# stm32l021.net
KiCad netlist of a schematic drawn in EAGLE
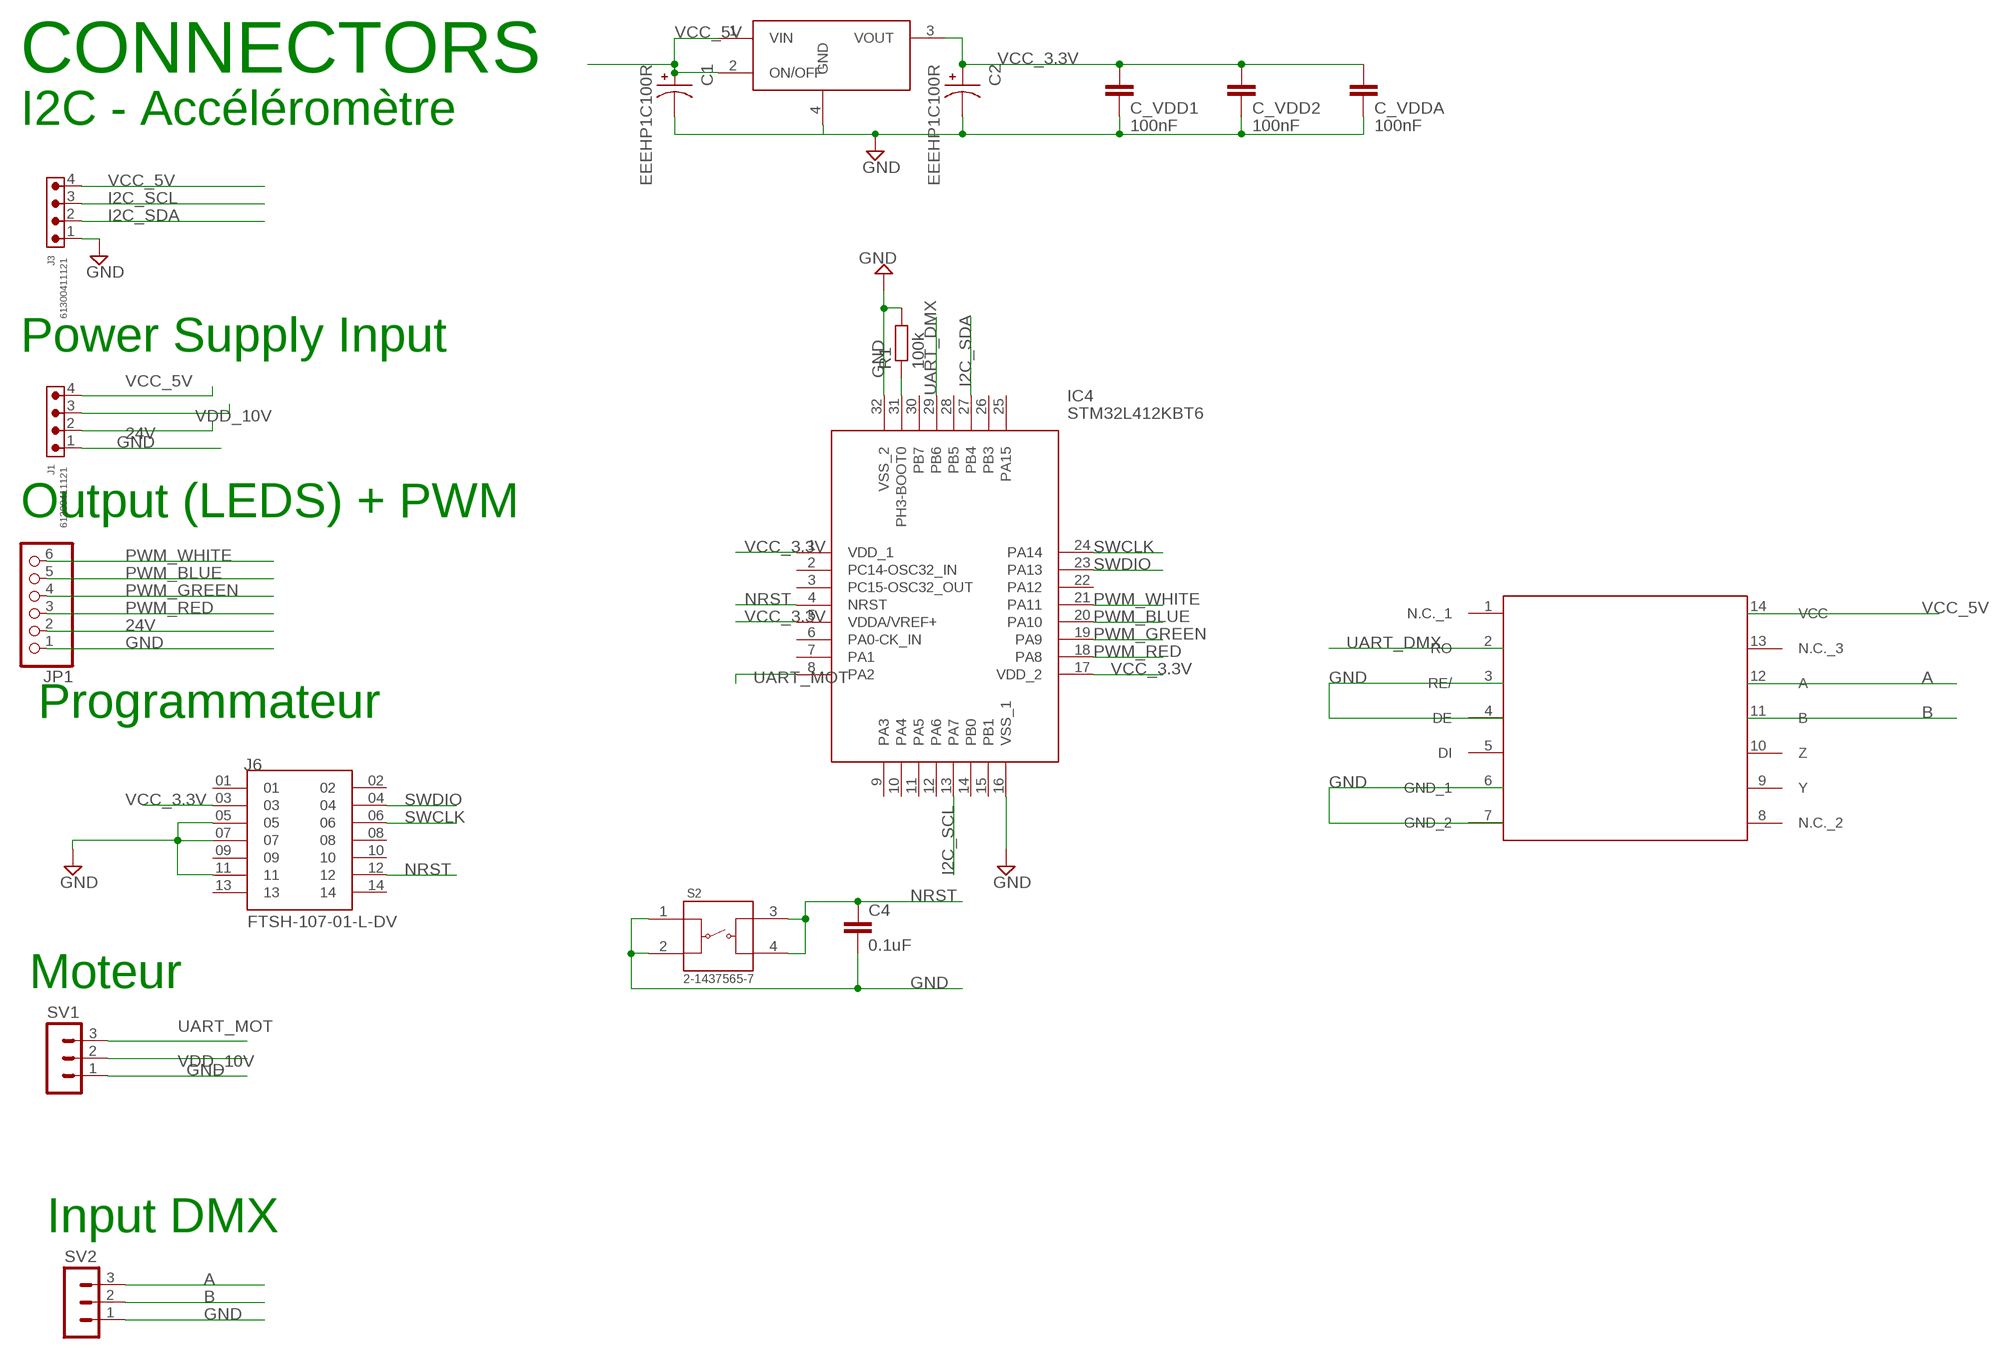
[diagram p0: schematic, sheet 1]

(export (version "E")
  (design (tool "Eeschema 10.0.6"))
  (components
    (comp (ref "C1")
      (value "EEEHP1C100R")
      (footprint "eagle-import:CAP_EEEHP1C100R")
      (fields (field (name "MF") "Panasonic"))
      (libsource (lib "eagle-import") (part "EEEHP1C100R"))
    )
    (comp (ref "C2")
      (value "EEEHP1C100R")
      (footprint "eagle-import:CAP_EEEHP1C100R")
      (fields (field (name "MF") "Panasonic"))
      (libsource (lib "eagle-import") (part "EEEHP1C100R"))
    )
    (comp (ref "C4")
      (value "0.1uF")
      (footprint "eagle-import:C0603")
      (libsource (lib "eagle-import") (part "C-EUC0603"))
    )
    (comp (ref "C_VDD1")
      (value "100nF")
      (footprint "eagle-import:C0603")
      (libsource (lib "eagle-import") (part "C-EUC0603"))
    )
    (comp (ref "C_VDD2")
      (value "100nF")
      (footprint "eagle-import:C0603")
      (libsource (lib "eagle-import") (part "C-EUC0603"))
    )
    (comp (ref "C_VDDA")
      (value "100nF")
      (footprint "eagle-import:C0603")
      (libsource (lib "eagle-import") (part "C-EUC0603"))
    )
    (comp (ref "IC4")
      (value "STM32L412KBT6")
      (footprint "eagle-import:QFP80P900X900X160-32N")
      (fields (field (name "MOUSER_PART_NUMBER") "511-STM32L412KBT6"))
      (libsource (lib "eagle-import") (part "STM32L412KBT6"))
    )
    (comp (ref "J1")
      (value "61300411121")
      (footprint "eagle-import:61300411121")
      (libsource (lib "eagle-import") (part "6130XX11121_61300411121"))
    )
    (comp (ref "J3")
      (value "61300411121")
      (footprint "eagle-import:61300411121")
      (libsource (lib "eagle-import") (part "6130XX11121_61300411121"))
    )
    (comp (ref "J6")
      (value "FTSH-107-01-L-DV")
      (footprint "eagle-import:SAMTEC_FTSH-107-01-L-DV")
      (fields (field (name "MANUFACTURER") "Samtec"))
      (libsource (lib "eagle-import") (part "FTSH-107-01-L-DV"))
    )
    (comp (ref "JP1")
      (value "PINHD-1X6")
      (footprint "eagle-import:1X06")
      (libsource (lib "eagle-import") (part "PINHD-1X6"))
    )
    (comp (ref "R1")
      (value "100k")
      (footprint "eagle-import:R0603")
      (libsource (lib "eagle-import") (part "R-EU_R0603"))
    )
    (comp (ref "S2")
      (value "2-1437565-7")
      (footprint "eagle-import:SW_2-1437565-7")
      (fields (field (name "MF") "TE Connectivity") (field (name "MP") "FSM2JSMA"))
      (libsource (lib "eagle-import") (part "2-1437565-7"))
    )
    (comp (ref "SV1")
      (value "MA03-1")
      (footprint "eagle-import:MA03-1")
      (libsource (lib "eagle-import") (part "MA03-1"))
    )
    (comp (ref "SV2")
      (value "MA03-1")
      (footprint "eagle-import:MA03-1")
      (libsource (lib "eagle-import") (part "MA03-1"))
    )
    (comp (ref "U$1")
      (value "NCV33375ST3.3T3G")
      (footprint "eagle-import:VREG_NCP1117STAT3G")
      (libsource (lib "eagle-import") (part "NCV33375ST3.3T3G"))
    )
    (comp (ref "U1")
      (value "SOIC127P600X175-14N")
      (footprint "eagle-import:SOIC127P600X175-14N")
      (fields (field (name "MANUFACTURER") "Maxim Integrated"))
      (libsource (lib "eagle-import") (part "SOIC127P600X175-14N"))
    )
  )
  (nets
    (net (code "1") (name "/24V") (class "Default")
      (node (ref "J1") (pin "2") (pinfunction "2_2") (pintype "passive"))
      (node (ref "JP1") (pin "2") (pinfunction "2_2") (pintype "passive"))
    )
    (net (code "2") (name "/A") (class "Default")
      (node (ref "SV2") (pin "3") (pinfunction "3_3") (pintype "passive"))
      (node (ref "U1") (pin "12") (pinfunction "A_12") (pintype "bidirectional"))
    )
    (net (code "3") (name "/B") (class "Default")
      (node (ref "SV2") (pin "2") (pinfunction "2_2") (pintype "passive"))
      (node (ref "U1") (pin "11") (pinfunction "B_11") (pintype "bidirectional"))
    )
    (net (code "4") (name "/I2C_SCL") (class "Default")
      (node (ref "IC4") (pin "13") (pinfunction "PA7_13") (pintype "bidirectional"))
      (node (ref "J3") (pin "3") (pinfunction "3_3") (pintype "passive"))
    )
    (net (code "5") (name "/I2C_SDA") (class "Default")
      (node (ref "IC4") (pin "27") (pinfunction "PB4_27") (pintype "bidirectional"))
      (node (ref "J3") (pin "2") (pinfunction "2_2") (pintype "passive"))
    )
    (net (code "6") (name "/NRST") (class "Default")
      (node (ref "C4") (pin "1") (pinfunction "1_1") (pintype "passive"))
      (node (ref "IC4") (pin "4") (pinfunction "NRST_4") (pintype "input"))
      (node (ref "J6") (pin "12") (pinfunction "12_12") (pintype "passive"))
      (node (ref "S2") (pin "3") (pinfunction "3_3") (pintype "passive"))
      (node (ref "S2") (pin "4") (pinfunction "4_4") (pintype "passive"))
    )
    (net (code "7") (name "/PWM_BLUE") (class "Default")
      (node (ref "IC4") (pin "20") (pinfunction "PA10_20") (pintype "bidirectional"))
      (node (ref "JP1") (pin "5") (pinfunction "5_5") (pintype "passive"))
    )
    (net (code "8") (name "/PWM_GREEN") (class "Default")
      (node (ref "IC4") (pin "19") (pinfunction "PA9_19") (pintype "bidirectional"))
      (node (ref "JP1") (pin "4") (pinfunction "4_4") (pintype "passive"))
    )
    (net (code "9") (name "/PWM_RED") (class "Default")
      (node (ref "IC4") (pin "18") (pinfunction "PA8_18") (pintype "bidirectional"))
      (node (ref "JP1") (pin "3") (pinfunction "3_3") (pintype "passive"))
    )
    (net (code "10") (name "/PWM_WHITE") (class "Default")
      (node (ref "IC4") (pin "21") (pinfunction "PA11_21") (pintype "bidirectional"))
      (node (ref "JP1") (pin "6") (pinfunction "6_6") (pintype "passive"))
    )
    (net (code "11") (name "/SWCLK") (class "Default")
      (node (ref "IC4") (pin "24") (pinfunction "PA14_24") (pintype "bidirectional"))
      (node (ref "J6") (pin "06") (pinfunction "06_06") (pintype "passive"))
    )
    (net (code "12") (name "/SWDIO") (class "Default")
      (node (ref "IC4") (pin "23") (pinfunction "PA13_23") (pintype "bidirectional"))
      (node (ref "J6") (pin "04") (pinfunction "04_04") (pintype "passive"))
    )
    (net (code "13") (name "/UART_DMX") (class "Default")
      (node (ref "IC4") (pin "29") (pinfunction "PB6_29") (pintype "bidirectional"))
      (node (ref "U1") (pin "2") (pinfunction "RO_2") (pintype "bidirectional"))
    )
    (net (code "14") (name "/UART_MOT") (class "Default")
      (node (ref "IC4") (pin "8") (pinfunction "PA2_8") (pintype "bidirectional"))
      (node (ref "SV1") (pin "3") (pinfunction "3_3") (pintype "passive"))
    )
    (net (code "15") (name "/VCC_3.3V") (class "Default")
      (node (ref "C2") (pin "1") (pinfunction "1_1") (pintype "passive"))
      (node (ref "C_VDD1") (pin "1") (pinfunction "1_1") (pintype "passive"))
      (node (ref "C_VDD2") (pin "1") (pinfunction "1_1") (pintype "passive"))
      (node (ref "C_VDDA") (pin "1") (pinfunction "1_1") (pintype "passive"))
      (node (ref "IC4") (pin "1") (pinfunction "VDD_1_1") (pintype "power_in"))
      (node (ref "IC4") (pin "17") (pinfunction "VDD_2_17") (pintype "power_in"))
      (node (ref "IC4") (pin "5") (pinfunction "VDDA/VREF+_5") (pintype "power_in"))
      (node (ref "J6") (pin "03") (pinfunction "03_03") (pintype "passive"))
      (node (ref "U$1") (pin "3") (pinfunction "VOUT_3") (pintype "bidirectional"))
    )
    (net (code "16") (name "/VCC_5V") (class "Default")
      (node (ref "C1") (pin "1") (pinfunction "1_1") (pintype "passive"))
      (node (ref "J1") (pin "4") (pinfunction "4_4") (pintype "passive"))
      (node (ref "J3") (pin "4") (pinfunction "4_4") (pintype "passive"))
      (node (ref "U$1") (pin "1") (pinfunction "VIN_1") (pintype "bidirectional"))
      (node (ref "U$1") (pin "2") (pinfunction "ON/OFF_2") (pintype "bidirectional"))
      (node (ref "U1") (pin "14") (pinfunction "VCC_14") (pintype "bidirectional"))
    )
    (net (code "17") (name "/VDD_10V") (class "Default")
      (node (ref "J1") (pin "3") (pinfunction "3_3") (pintype "passive"))
      (node (ref "SV1") (pin "2") (pinfunction "2_2") (pintype "passive"))
    )
    (net (code "18") (name "GND") (class "Default")
      (node (ref "C1") (pin "2") (pinfunction "2_2") (pintype "passive"))
      (node (ref "C2") (pin "2") (pinfunction "2_2") (pintype "passive"))
      (node (ref "C4") (pin "2") (pinfunction "2_2") (pintype "passive"))
      (node (ref "C_VDD1") (pin "2") (pinfunction "2_2") (pintype "passive"))
      (node (ref "C_VDD2") (pin "2") (pinfunction "2_2") (pintype "passive"))
      (node (ref "C_VDDA") (pin "2") (pinfunction "2_2") (pintype "passive"))
      (node (ref "IC4") (pin "16") (pinfunction "VSS_1_16") (pintype "power_in"))
      (node (ref "IC4") (pin "32") (pinfunction "VSS_2_32") (pintype "power_in"))
      (node (ref "J1") (pin "1") (pinfunction "1_1") (pintype "passive"))
      (node (ref "J3") (pin "1") (pinfunction "1_1") (pintype "passive"))
      (node (ref "J6") (pin "05") (pinfunction "05_05") (pintype "passive"))
      (node (ref "J6") (pin "07") (pinfunction "07_07") (pintype "passive"))
      (node (ref "J6") (pin "11") (pinfunction "11_11") (pintype "passive"))
      (node (ref "JP1") (pin "1") (pinfunction "1_1") (pintype "passive"))
      (node (ref "R1") (pin "2") (pinfunction "2_2") (pintype "passive"))
      (node (ref "S2") (pin "1") (pinfunction "1_1") (pintype "passive"))
      (node (ref "S2") (pin "2") (pinfunction "2_2") (pintype "passive"))
      (node (ref "SV1") (pin "1") (pinfunction "1_1") (pintype "passive"))
      (node (ref "SV2") (pin "1") (pinfunction "1_1") (pintype "passive"))
      (node (ref "U$1") (pin "4") (pinfunction "GND_4") (pintype "bidirectional"))
      (node (ref "U1") (pin "3") (pinfunction "RE/_3") (pintype "bidirectional"))
      (node (ref "U1") (pin "4") (pinfunction "DE_4") (pintype "bidirectional"))
      (node (ref "U1") (pin "6") (pinfunction "GND_1_6") (pintype "bidirectional"))
      (node (ref "U1") (pin "7") (pinfunction "GND_2_7") (pintype "bidirectional"))
    )
    (net (code "19") (name "Net-(IC4-PH3-BOOT0)") (class "Default")
      (node (ref "IC4") (pin "31") (pinfunction "PH3-BOOT0_31") (pintype "bidirectional"))
      (node (ref "R1") (pin "1") (pinfunction "1_1") (pintype "passive"))
    )
    (net (code "20") (name "unconnected-(IC4-PA0-CK_IN-Pad6)") (class "Default")
      (node (ref "IC4") (pin "6") (pinfunction "PA0-CK_IN_6") (pintype "bidirectional"))
    )
    (net (code "21") (name "unconnected-(IC4-PA1-Pad7)") (class "Default")
      (node (ref "IC4") (pin "7") (pinfunction "PA1_7") (pintype "bidirectional"))
    )
    (net (code "22") (name "unconnected-(IC4-PA3-Pad9)") (class "Default")
      (node (ref "IC4") (pin "9") (pinfunction "PA3_9") (pintype "bidirectional"))
    )
    (net (code "23") (name "unconnected-(IC4-PA4-Pad10)") (class "Default")
      (node (ref "IC4") (pin "10") (pinfunction "PA4_10") (pintype "bidirectional"))
    )
    (net (code "24") (name "unconnected-(IC4-PA5-Pad11)") (class "Default")
      (node (ref "IC4") (pin "11") (pinfunction "PA5_11") (pintype "bidirectional"))
    )
    (net (code "25") (name "unconnected-(IC4-PA6-Pad12)") (class "Default")
      (node (ref "IC4") (pin "12") (pinfunction "PA6_12") (pintype "bidirectional"))
    )
    (net (code "26") (name "unconnected-(IC4-PA12-Pad22)") (class "Default")
      (node (ref "IC4") (pin "22") (pinfunction "PA12_22") (pintype "bidirectional"))
    )
    (net (code "27") (name "unconnected-(IC4-PA15-Pad25)") (class "Default")
      (node (ref "IC4") (pin "25") (pinfunction "PA15_25") (pintype "bidirectional"))
    )
    (net (code "28") (name "unconnected-(IC4-PB0-Pad14)") (class "Default")
      (node (ref "IC4") (pin "14") (pinfunction "PB0_14") (pintype "bidirectional"))
    )
    (net (code "29") (name "unconnected-(IC4-PB1-Pad15)") (class "Default")
      (node (ref "IC4") (pin "15") (pinfunction "PB1_15") (pintype "bidirectional"))
    )
    (net (code "30") (name "unconnected-(IC4-PB3-Pad26)") (class "Default")
      (node (ref "IC4") (pin "26") (pinfunction "PB3_26") (pintype "bidirectional"))
    )
    (net (code "31") (name "unconnected-(IC4-PB5-Pad28)") (class "Default")
      (node (ref "IC4") (pin "28") (pinfunction "PB5_28") (pintype "bidirectional"))
    )
    (net (code "32") (name "unconnected-(IC4-PB7-Pad30)") (class "Default")
      (node (ref "IC4") (pin "30") (pinfunction "PB7_30") (pintype "bidirectional"))
    )
    (net (code "33") (name "unconnected-(IC4-PC14-OSC32_IN-Pad2)") (class "Default")
      (node (ref "IC4") (pin "2") (pinfunction "PC14-OSC32_IN_2") (pintype "bidirectional"))
    )
    (net (code "34") (name "unconnected-(IC4-PC15-OSC32_OUT-Pad3)") (class "Default")
      (node (ref "IC4") (pin "3") (pinfunction "PC15-OSC32_OUT_3") (pintype "bidirectional"))
    )
    (net (code "35") (name "unconnected-(J6-Pad01)") (class "Default")
      (node (ref "J6") (pin "01") (pinfunction "01_01") (pintype "passive"))
    )
    (net (code "36") (name "unconnected-(J6-Pad02)") (class "Default")
      (node (ref "J6") (pin "02") (pinfunction "02_02") (pintype "passive"))
    )
    (net (code "37") (name "unconnected-(J6-Pad08)") (class "Default")
      (node (ref "J6") (pin "08") (pinfunction "08_08") (pintype "passive"))
    )
    (net (code "38") (name "unconnected-(J6-Pad09)") (class "Default")
      (node (ref "J6") (pin "09") (pinfunction "09_09") (pintype "passive"))
    )
    (net (code "39") (name "unconnected-(J6-Pad10)") (class "Default")
      (node (ref "J6") (pin "10") (pinfunction "10_10") (pintype "passive"))
    )
    (net (code "40") (name "unconnected-(J6-Pad13)") (class "Default")
      (node (ref "J6") (pin "13") (pinfunction "13_13") (pintype "passive"))
    )
    (net (code "41") (name "unconnected-(J6-Pad14)") (class "Default")
      (node (ref "J6") (pin "14") (pinfunction "14_14") (pintype "passive"))
    )
    (net (code "42") (name "unconnected-(U1-DI-Pad5)") (class "Default")
      (node (ref "U1") (pin "5") (pinfunction "DI_5") (pintype "bidirectional"))
    )
    (net (code "43") (name "unconnected-(U1-N.C._1-Pad1)") (class "Default")
      (node (ref "U1") (pin "1") (pinfunction "N.C._1_1") (pintype "bidirectional"))
    )
    (net (code "44") (name "unconnected-(U1-N.C._2-Pad8)") (class "Default")
      (node (ref "U1") (pin "8") (pinfunction "N.C._2_8") (pintype "bidirectional"))
    )
    (net (code "45") (name "unconnected-(U1-N.C._3-Pad13)") (class "Default")
      (node (ref "U1") (pin "13") (pinfunction "N.C._3_13") (pintype "bidirectional"))
    )
    (net (code "46") (name "unconnected-(U1-Y-Pad9)") (class "Default")
      (node (ref "U1") (pin "9") (pinfunction "Y_9") (pintype "bidirectional"))
    )
    (net (code "47") (name "unconnected-(U1-Z-Pad10)") (class "Default")
      (node (ref "U1") (pin "10") (pinfunction "Z_10") (pintype "bidirectional"))
    )
  )
)
